# Amplifier.net
KiCad netlist of a schematic drawn in Altium Designer
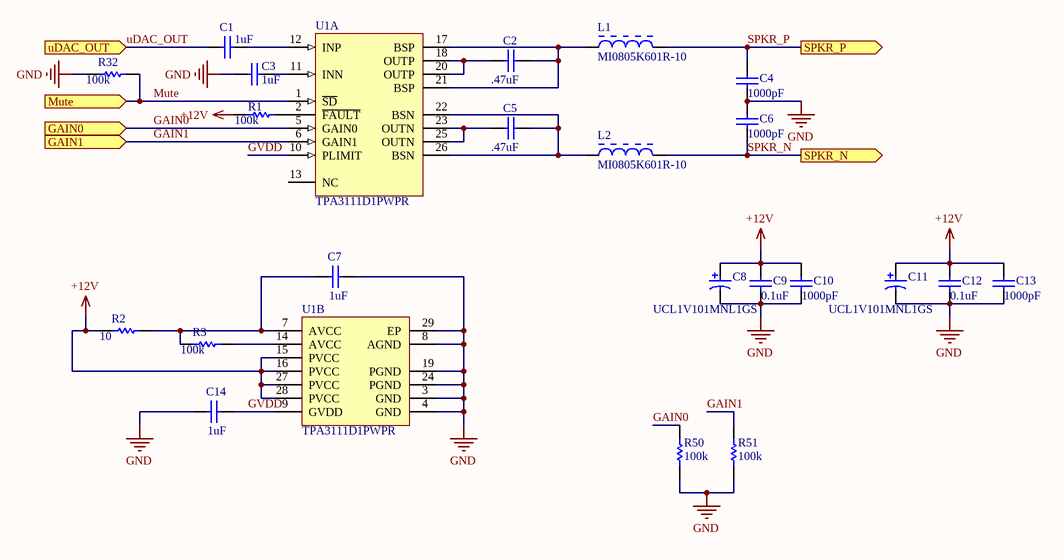
[diagram p0: Amplifier.SchDoc]

(export (version "E")
  (design (tool "Eeschema 10.0.6"))
  (components
    (comp (ref "C1")
      (value "1uF")
      (footprint "CAPC0603(1608)100_L")
      (description "CAP 1uF 25V ±10% 0603 (1608 Metric) Thickness 1mm SMD")
      (fields (field (name "TOLERANCE") "Â±10%"))
      (libsource (lib "Altium Content Vault") (part "CAP"))
    )
    (comp (ref "C2")
      (value ".47uF")
      (footprint "CAPC0805(2012)110_N")
      (description "CAP 470nF 50V ±20% 0805 (2012 Metric) Thickness 1.1mm SMD")
      (fields (field (name "TOLERANCE") "Â±20%"))
      (libsource (lib "Altium Content Vault") (part "CAP"))
    )
    (comp (ref "C3")
      (value "1uF")
      (footprint "CAPC0603(1608)100_L")
      (description "CAP 1uF 25V ±10% 0603 (1608 Metric) Thickness 1mm SMD")
      (fields (field (name "TOLERANCE") "Â±10%"))
      (libsource (lib "Altium Content Vault") (part "CAP"))
    )
    (comp (ref "C4")
      (value "1000pF")
      (footprint "CAPC0805(2012)145_L")
      (description "0805 (2012 Metric) Chip Capacitor")
      (libsource (lib "Altium Content Vault") (part "CAP_5"))
    )
    (comp (ref "C5")
      (value ".47uF")
      (footprint "CAPC0805(2012)110_N")
      (description "CAP 470nF 50V ±20% 0805 (2012 Metric) Thickness 1.1mm SMD")
      (fields (field (name "TOLERANCE") "Â±20%"))
      (libsource (lib "Altium Content Vault") (part "CAP"))
    )
    (comp (ref "C6")
      (value "1000pF")
      (footprint "CAPC0805(2012)145_L")
      (description "0805 (2012 Metric) Chip Capacitor")
      (libsource (lib "Altium Content Vault") (part "CAP_5"))
    )
    (comp (ref "C7")
      (value "1uF")
      (footprint "CAPC0603(1608)100_L")
      (description "CAP 1uF 25V ±10% 0603 (1608 Metric) Thickness 1mm SMD")
      (fields (field (name "TOLERANCE") "Â±10%"))
      (libsource (lib "Altium Content Vault") (part "CAP"))
    )
    (comp (ref "C8")
      (value "UCL1V101MNL1GS")
      (footprint "NIC-UCL1V101MNL1GS_L")
      (fields (field (name "MANUFACTURER") "Nichicon") (field (name "TOLERANCE") "20%"))
      (libsource (lib "Altium Content Vault") (part "CAP-P-2"))
    )
    (comp (ref "C9")
      (value "0.1uF")
      (footprint "CAPC0805(2012)145_L")
      (description "0805 (2012 Metric) Chip Capacitor")
      (libsource (lib "Altium Content Vault") (part "CAP_5"))
    )
    (comp (ref "C10")
      (value "1000pF")
      (footprint "CAPC0805(2012)145_L")
      (description "0805 (2012 Metric) Chip Capacitor")
      (libsource (lib "Altium Content Vault") (part "CAP_5"))
    )
    (comp (ref "C11")
      (value "UCL1V101MNL1GS")
      (footprint "NIC-UCL1V101MNL1GS_L")
      (fields (field (name "MANUFACTURER") "Nichicon") (field (name "TOLERANCE") "20%"))
      (libsource (lib "Altium Content Vault") (part "CAP-P-2"))
    )
    (comp (ref "C12")
      (value "0.1uF")
      (footprint "CAPC0805(2012)145_L")
      (description "0805 (2012 Metric) Chip Capacitor")
      (libsource (lib "Altium Content Vault") (part "CAP_5"))
    )
    (comp (ref "C13")
      (value "1000pF")
      (footprint "CAPC0805(2012)145_L")
      (description "0805 (2012 Metric) Chip Capacitor")
      (libsource (lib "Altium Content Vault") (part "CAP_5"))
    )
    (comp (ref "C14")
      (value "1uF")
      (footprint "CAPC0603(1608)100_L")
      (description "CAP 1uF 25V ±10% 0603 (1608 Metric) Thickness 1mm SMD")
      (fields (field (name "TOLERANCE") "Â±10%"))
      (libsource (lib "Altium Content Vault") (part "CAP"))
    )
    (comp (ref "L1")
      (value "MI0805K601R-10")
      (footprint "LIRD-MI0805K601R-10-2_V")
      (fields (field (name "MANUFACTURER") "Laird"))
      (libsource (lib "Altium Content Vault") (part "IND-FB-2"))
    )
    (comp (ref "L2")
      (value "MI0805K601R-10")
      (footprint "LIRD-MI0805K601R-10-2_V")
      (fields (field (name "MANUFACTURER") "Laird"))
      (libsource (lib "Altium Content Vault") (part "IND-FB-2"))
    )
    (comp (ref "R1")
      (value "100k")
      (footprint "RESC0805(2012)_L")
      (description "0805 (2012 Metric) Chip Resistor")
      (fields (field (name "Comment") "100K"))
      (libsource (lib "Altium Content Vault") (part "RES_3"))
    )
    (comp (ref "R2")
      (value "10")
      (footprint "RESC0805(2012)_L")
      (description "0805 (2012 Metric) Chip Resistor")
      (fields (field (name "Comment") "10R"))
      (libsource (lib "Altium Content Vault") (part "RES_3"))
    )
    (comp (ref "R3")
      (value "100k")
      (footprint "RESC0805(2012)_L")
      (description "0805 (2012 Metric) Chip Resistor")
      (libsource (lib "Altium Content Vault") (part "RES_3"))
    )
    (comp (ref "R32")
      (value "100k")
      (footprint "RESC0805(2012)_L")
      (description "0805 (2012 Metric) Chip Resistor")
      (fields (field (name "Comment") "100K"))
      (libsource (lib "Altium Content Vault") (part "RES_3"))
    )
    (comp (ref "R50")
      (value "100k")
      (footprint "RESC0805(2012)_L")
      (description "0805 (2012 Metric) Chip Resistor")
      (fields (field (name "Comment") "100K"))
      (libsource (lib "Altium Content Vault") (part "RES_3"))
    )
    (comp (ref "R51")
      (value "100k")
      (footprint "RESC0805(2012)_L")
      (description "0805 (2012 Metric) Chip Resistor")
      (fields (field (name "Comment") "100K"))
      (libsource (lib "Altium Content Vault") (part "RES_3"))
    )
    (comp (ref "U1")
      (value "TPA3111D1PWPR")
      (footprint "TI-PWP28-5720X1950TP_Q")
      (fields (field (name "MANUFACTURER") "Texas Instruments"))
      (libsource (lib "Integrated_Library - 28.09.18 - 20.02") (part "CMP-0994-00250-1"))
    )
  )
  (nets
    (net (code "1") (name "+12V") (class "Default")
      (node (ref "C10") (pin "2") (pinfunction "2_2") (pintype "passive"))
      (node (ref "C11") (pin "1") (pinfunction "1_1") (pintype "passive"))
      (node (ref "C12") (pin "2") (pinfunction "2_2") (pintype "passive"))
      (node (ref "C13") (pin "2") (pinfunction "2_2") (pintype "passive"))
      (node (ref "C8") (pin "1") (pinfunction "1_1") (pintype "passive"))
      (node (ref "C9") (pin "2") (pinfunction "2_2") (pintype "passive"))
      (node (ref "R1") (pin "1") (pinfunction "1_1") (pintype "passive"))
      (node (ref "R2") (pin "1") (pinfunction "1_1") (pintype "passive"))
      (node (ref "U1") (pin "15") (pinfunction "PVCC_15") (pintype "power_in"))
      (node (ref "U1") (pin "16") (pinfunction "PVCC_16") (pintype "power_in"))
      (node (ref "U1") (pin "27") (pinfunction "PVCC_27") (pintype "power_in"))
      (node (ref "U1") (pin "28") (pinfunction "PVCC_28") (pintype "power_in"))
    )
    (net (code "2") (name "/GAIN0") (class "Default")
      (node (ref "R50") (pin "2") (pinfunction "2_2") (pintype "passive"))
      (node (ref "U1") (pin "5") (pinfunction "GAIN0_5") (pintype "input"))
    )
    (net (code "3") (name "/GAIN1") (class "Default")
      (node (ref "R51") (pin "2") (pinfunction "2_2") (pintype "passive"))
      (node (ref "U1") (pin "6") (pinfunction "GAIN1_6") (pintype "input"))
    )
    (net (code "4") (name "/GVDD") (class "Default")
      (node (ref "C14") (pin "2") (pinfunction "2_2") (pintype "passive"))
      (node (ref "U1") (pin "10") (pinfunction "PLIMIT_10") (pintype "input"))
      (node (ref "U1") (pin "9") (pinfunction "GVDD_9") (pintype "power_in"))
    )
    (net (code "5") (name "/Mute") (class "Default")
      (node (ref "R32") (pin "2") (pinfunction "2_2") (pintype "passive"))
      (node (ref "U1") (pin "1") (pinfunction "~{SD}_1") (pintype "input"))
    )
    (net (code "6") (name "/SPKR_N") (class "Default")
      (node (ref "C6") (pin "1") (pinfunction "1_1") (pintype "passive"))
      (node (ref "L2") (pin "2") (pinfunction "2_2") (pintype "passive"))
    )
    (net (code "7") (name "/SPKR_P") (class "Default")
      (node (ref "C4") (pin "2") (pinfunction "2_2") (pintype "passive"))
      (node (ref "L1") (pin "2") (pinfunction "2_2") (pintype "passive"))
    )
    (net (code "8") (name "/uDAC_OUT") (class "Default")
      (node (ref "C1") (pin "1") (pinfunction "1_1") (pintype "passive"))
    )
    (net (code "9") (name "GND") (class "Default")
      (node (ref "C10") (pin "1") (pinfunction "1_1") (pintype "passive"))
      (node (ref "C11") (pin "2") (pinfunction "2_2") (pintype "passive"))
      (node (ref "C12") (pin "1") (pinfunction "1_1") (pintype "passive"))
      (node (ref "C13") (pin "1") (pinfunction "1_1") (pintype "passive"))
      (node (ref "C14") (pin "1") (pinfunction "1_1") (pintype "passive"))
      (node (ref "C3") (pin "1") (pinfunction "1_1") (pintype "passive"))
      (node (ref "C4") (pin "1") (pinfunction "1_1") (pintype "passive"))
      (node (ref "C6") (pin "2") (pinfunction "2_2") (pintype "passive"))
      (node (ref "C7") (pin "2") (pinfunction "2_2") (pintype "passive"))
      (node (ref "C8") (pin "2") (pinfunction "2_2") (pintype "passive"))
      (node (ref "C9") (pin "1") (pinfunction "1_1") (pintype "passive"))
      (node (ref "R32") (pin "1") (pinfunction "1_1") (pintype "passive"))
      (node (ref "R50") (pin "1") (pinfunction "1_1") (pintype "passive"))
      (node (ref "R51") (pin "1") (pinfunction "1_1") (pintype "passive"))
      (node (ref "U1") (pin "19") (pinfunction "PGND_19") (pintype "power_in"))
      (node (ref "U1") (pin "24") (pinfunction "PGND_24") (pintype "power_in"))
      (node (ref "U1") (pin "29") (pinfunction "EP_29") (pintype "power_in"))
      (node (ref "U1") (pin "3") (pinfunction "GND_3") (pintype "power_in"))
      (node (ref "U1") (pin "4") (pinfunction "GND_4") (pintype "power_in"))
      (node (ref "U1") (pin "8") (pinfunction "AGND_8") (pintype "power_in"))
    )
    (net (code "10") (name "Net-(C2-Pad1)") (class "Default")
      (node (ref "C2") (pin "1") (pinfunction "1_1") (pintype "passive"))
      (node (ref "U1") (pin "18") (pinfunction "OUTP_18") (pintype "tri_state"))
      (node (ref "U1") (pin "20") (pinfunction "OUTP_20") (pintype "tri_state"))
    )
    (net (code "11") (name "Net-(C2-Pad2)") (class "Default")
      (node (ref "C2") (pin "2") (pinfunction "2_2") (pintype "passive"))
      (node (ref "L1") (pin "1") (pinfunction "1_1") (pintype "passive"))
      (node (ref "U1") (pin "17") (pinfunction "BSP_17") (pintype "passive"))
      (node (ref "U1") (pin "21") (pinfunction "BSP_21") (pintype "passive"))
    )
    (net (code "12") (name "Net-(C5-Pad1)") (class "Default")
      (node (ref "C5") (pin "1") (pinfunction "1_1") (pintype "passive"))
      (node (ref "U1") (pin "23") (pinfunction "OUTN_23") (pintype "tri_state"))
      (node (ref "U1") (pin "25") (pinfunction "OUTN_25") (pintype "tri_state"))
    )
    (net (code "13") (name "Net-(C5-Pad2)") (class "Default")
      (node (ref "C5") (pin "2") (pinfunction "2_2") (pintype "passive"))
      (node (ref "L2") (pin "1") (pinfunction "1_1") (pintype "passive"))
      (node (ref "U1") (pin "22") (pinfunction "BSN_22") (pintype "passive"))
      (node (ref "U1") (pin "26") (pinfunction "BSN_26") (pintype "passive"))
    )
    (net (code "14") (name "Net-(C7-Pad1)") (class "Default")
      (node (ref "C7") (pin "1") (pinfunction "1_1") (pintype "passive"))
      (node (ref "R2") (pin "2") (pinfunction "2_2") (pintype "passive"))
      (node (ref "R3") (pin "1") (pinfunction "1_1") (pintype "passive"))
      (node (ref "U1") (pin "7") (pinfunction "AVCC_7") (pintype "power_in"))
    )
    (net (code "15") (name "Net-(R3-Pad2)") (class "Default")
      (node (ref "R3") (pin "2") (pinfunction "2_2") (pintype "passive"))
      (node (ref "U1") (pin "14") (pinfunction "AVCC_14") (pintype "power_in"))
    )
    (net (code "16") (name "Net-(U1A-INN)") (class "Default")
      (node (ref "C3") (pin "2") (pinfunction "2_2") (pintype "passive"))
      (node (ref "U1") (pin "11") (pinfunction "INN_11") (pintype "input"))
    )
    (net (code "17") (name "Net-(U1A-INP)") (class "Default")
      (node (ref "C1") (pin "2") (pinfunction "2_2") (pintype "passive"))
      (node (ref "U1") (pin "12") (pinfunction "INP_12") (pintype "input"))
    )
    (net (code "18") (name "Net-(U1A-~{FAULT})") (class "Default")
      (node (ref "R1") (pin "2") (pinfunction "2_2") (pintype "passive"))
      (node (ref "U1") (pin "2") (pinfunction "~{FAULT}_2") (pintype "open_collector"))
    )
    (net (code "19") (name "unconnected-(U1A-NC-Pad13)") (class "Default")
      (node (ref "U1") (pin "13") (pinfunction "NC_13") (pintype "passive"))
    )
  )
)
